# balun.net
KiCad netlist of a schematic drawn in EAGLE
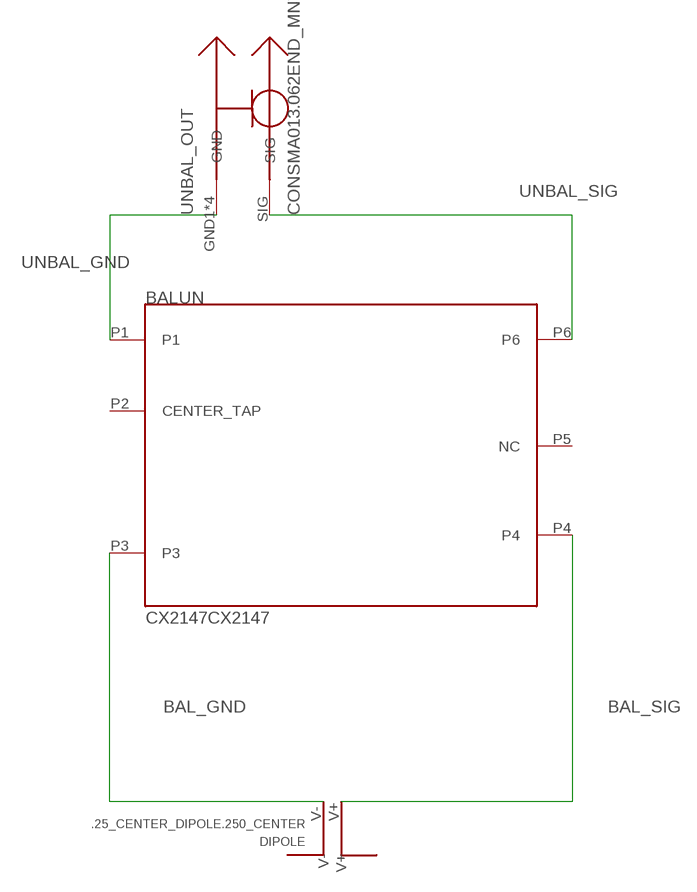
[diagram p0: schematic, sheet 1]

(export (version "E")
  (design (tool "Eeschema 10.0.6"))
  (components
    (comp (ref "BALUN")
      (value "CX2147CX2147")
      (footprint "eagle-import:6-SMD")
      (libsource (lib "eagle-import") (part "CX2147CX2147"))
    )
    (comp (ref "DIPOLE")
      (value ".25_CENTER_DIPOLE.250_CENTER")
      (footprint "eagle-import:.25_SPACING")
      (libsource (lib "eagle-import") (part ".25_CENTER_DIPOLE.250_CENTER"))
    )
    (comp (ref "UNBAL_OUT")
      (value "CONSMA013.062END_MNT")
      (footprint "eagle-import:SMA_EDGE_MNT")
      (libsource (lib "eagle-import") (part "CONSMA013.062END_MNT"))
    )
  )
  (nets
    (net (code "1") (name "/BAL_GND") (class "Default")
      (node (ref "BALUN") (pin "P3") (pinfunction "P3_P3") (pintype "bidirectional"))
      (node (ref "DIPOLE") (pin "V-") (pinfunction "V-_V-") (pintype "bidirectional"))
    )
    (net (code "2") (name "/BAL_SIG") (class "Default")
      (node (ref "BALUN") (pin "P4") (pinfunction "P4_P4") (pintype "bidirectional"))
      (node (ref "DIPOLE") (pin "V+") (pinfunction "V+_V+") (pintype "bidirectional"))
    )
    (net (code "3") (name "/UNBAL_GND") (class "Default")
      (node (ref "BALUN") (pin "P1") (pinfunction "P1_P1") (pintype "bidirectional"))
      (node (ref "UNBAL_OUT") (pin "GND1") (pinfunction "GND_GND1") (pintype "bidirectional"))
      (node (ref "UNBAL_OUT") (pin "GND2") (pinfunction "GND_GND2") (pintype "bidirectional"))
      (node (ref "UNBAL_OUT") (pin "GND3") (pinfunction "GND_GND3") (pintype "bidirectional"))
      (node (ref "UNBAL_OUT") (pin "GND4") (pinfunction "GND_GND4") (pintype "bidirectional"))
    )
    (net (code "4") (name "/UNBAL_SIG") (class "Default")
      (node (ref "BALUN") (pin "P6") (pinfunction "P6_P6") (pintype "bidirectional"))
      (node (ref "UNBAL_OUT") (pin "SIG") (pinfunction "SIG_SIG") (pintype "bidirectional"))
    )
    (net (code "5") (name "unconnected-(BALUN-CENTER_TAP-PadP2)") (class "Default")
      (node (ref "BALUN") (pin "P2") (pinfunction "CENTER_TAP_P2") (pintype "bidirectional"))
    )
    (net (code "6") (name "unconnected-(BALUN-NC-PadP5)") (class "Default")
      (node (ref "BALUN") (pin "P5") (pinfunction "NC_P5") (pintype "bidirectional"))
    )
  )
)
